# Status_LEDS.net
KiCad netlist of a schematic drawn in Altium Designer
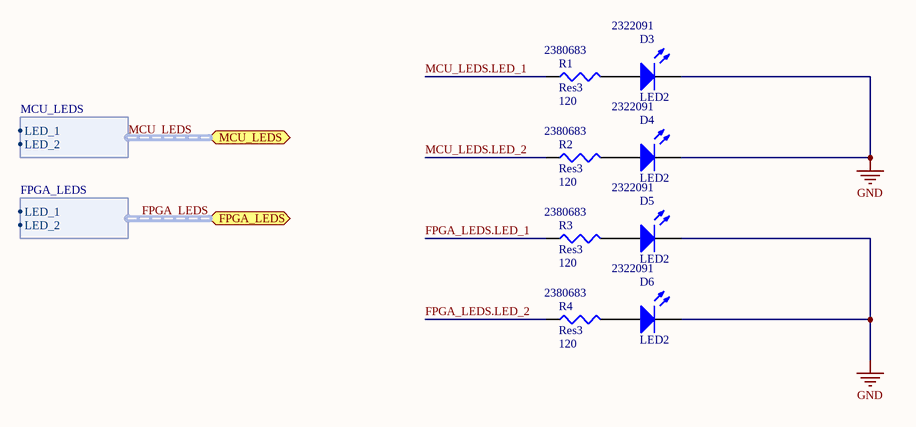
[diagram p0: Status_LEDS.SchDoc]

(export (version "E")
  (design (tool "Eeschema 10.0.6"))
  (components
    (comp (ref "D3")
      (value "LED2")
      (footprint "C1206")
      (description "Typical RED, GREEN, YELLOW, AMBER GaAs LED")
      (fields
        (field (name "SUPPLIER PART NUMBER 1") "2322091")
        (field (name "MANUFACTURER") "WURTH ELEKTRONIK")
        (field (name "MANUFACTURER PART NUMBER") "156120GS75300")
        (field (name "PUBLISHER") "Altium Limited")
      )
      (libsource (lib "Miscellaneous Devices") (part "LED2"))
    )
    (comp (ref "D4")
      (value "LED2")
      (footprint "C1206")
      (description "Typical RED, GREEN, YELLOW, AMBER GaAs LED")
      (fields
        (field (name "SUPPLIER PART NUMBER 1") "2322091")
        (field (name "MANUFACTURER") "WURTH ELEKTRONIK")
        (field (name "MANUFACTURER PART NUMBER") "156120GS75300")
        (field (name "PUBLISHER") "Altium Limited")
      )
      (libsource (lib "Miscellaneous Devices") (part "LED2"))
    )
    (comp (ref "D5")
      (value "LED2")
      (footprint "C1206")
      (description "Typical RED, GREEN, YELLOW, AMBER GaAs LED")
      (fields
        (field (name "SUPPLIER PART NUMBER 1") "2322091")
        (field (name "MANUFACTURER") "WURTH ELEKTRONIK")
        (field (name "MANUFACTURER PART NUMBER") "156120GS75300")
        (field (name "PUBLISHER") "Altium Limited")
      )
      (libsource (lib "Miscellaneous Devices") (part "LED2"))
    )
    (comp (ref "D6")
      (value "LED2")
      (footprint "C1206")
      (description "Typical RED, GREEN, YELLOW, AMBER GaAs LED")
      (fields
        (field (name "SUPPLIER PART NUMBER 1") "2322091")
        (field (name "MANUFACTURER") "WURTH ELEKTRONIK")
        (field (name "MANUFACTURER PART NUMBER") "156120GS75300")
        (field (name "PUBLISHER") "Altium Limited")
      )
      (libsource (lib "Miscellaneous Devices") (part "LED2"))
    )
    (comp (ref "R1")
      (value "Res3")
      (footprint "14-1210")
      (description "Resistor")
      (fields
        (field (name "ALTIUM_VALUE") "120")
        (field (name "SUPPLIER PART NUMBER 1") "2380683")
        (field (name "MANUFACTURER") "PANASONIC")
        (field (name "MANUFACTURER PART NUMBER") "ERJU14F1200U")
        (field (name "PUBLISHER") "Altium Limited")
      )
      (libsource (lib "Miscellaneous Devices") (part "Res3"))
    )
    (comp (ref "R2")
      (value "Res3")
      (footprint "14-1210")
      (description "Resistor")
      (fields
        (field (name "ALTIUM_VALUE") "120")
        (field (name "SUPPLIER PART NUMBER 1") "2380683")
        (field (name "MANUFACTURER") "PANASONIC")
        (field (name "MANUFACTURER PART NUMBER") "ERJU14F1200U")
        (field (name "PUBLISHER") "Altium Limited")
      )
      (libsource (lib "Miscellaneous Devices") (part "Res3"))
    )
    (comp (ref "R3")
      (value "Res3")
      (footprint "14-1210")
      (description "Resistor")
      (fields
        (field (name "ALTIUM_VALUE") "120")
        (field (name "SUPPLIER PART NUMBER 1") "2380683")
        (field (name "MANUFACTURER") "PANASONIC")
        (field (name "MANUFACTURER PART NUMBER") "ERJU14F1200U")
        (field (name "PUBLISHER") "Altium Limited")
      )
      (libsource (lib "Miscellaneous Devices") (part "Res3"))
    )
    (comp (ref "R4")
      (value "Res3")
      (footprint "14-1210")
      (description "Resistor")
      (fields
        (field (name "ALTIUM_VALUE") "120")
        (field (name "SUPPLIER PART NUMBER 1") "2380683")
        (field (name "MANUFACTURER") "PANASONIC")
        (field (name "MANUFACTURER PART NUMBER") "ERJU14F1200U")
        (field (name "PUBLISHER") "Altium Limited")
      )
      (libsource (lib "Miscellaneous Devices") (part "Res3"))
    )
  )
  (nets
    (net (code "3") (name "/FPGA_LEDS.LED_1") (class "Default")
      (node (ref "R3") (pin "1") (pinfunction "1_1") (pintype "passive"))
    )
    (net (code "4") (name "/FPGA_LEDS.LED_2") (class "Default")
      (node (ref "R4") (pin "1") (pinfunction "1_1") (pintype "passive"))
    )
    (net (code "6") (name "/MCU_LEDS.LED_1") (class "Default")
      (node (ref "R1") (pin "1") (pinfunction "1_1") (pintype "passive"))
    )
    (net (code "7") (name "/MCU_LEDS.LED_2") (class "Default")
      (node (ref "R2") (pin "1") (pinfunction "1_1") (pintype "passive"))
    )
    (net (code "9") (name "GND") (class "Default")
      (node (ref "D3") (pin "2") (pinfunction "K_2") (pintype "passive"))
      (node (ref "D4") (pin "2") (pinfunction "K_2") (pintype "passive"))
      (node (ref "D5") (pin "2") (pinfunction "K_2") (pintype "passive"))
      (node (ref "D6") (pin "2") (pinfunction "K_2") (pintype "passive"))
    )
    (net (code "10") (name "Net-(D3-A)") (class "Default")
      (node (ref "D3") (pin "1") (pinfunction "A_1") (pintype "passive"))
      (node (ref "R1") (pin "2") (pinfunction "2_2") (pintype "passive"))
    )
    (net (code "11") (name "Net-(D4-A)") (class "Default")
      (node (ref "D4") (pin "1") (pinfunction "A_1") (pintype "passive"))
      (node (ref "R2") (pin "2") (pinfunction "2_2") (pintype "passive"))
    )
    (net (code "12") (name "Net-(D5-A)") (class "Default")
      (node (ref "D5") (pin "1") (pinfunction "A_1") (pintype "passive"))
      (node (ref "R3") (pin "2") (pinfunction "2_2") (pintype "passive"))
    )
    (net (code "13") (name "Net-(D6-A)") (class "Default")
      (node (ref "D6") (pin "1") (pinfunction "A_1") (pintype "passive"))
      (node (ref "R4") (pin "2") (pinfunction "2_2") (pintype "passive"))
    )
  )
)
